# Top.net
KiCad netlist of a schematic drawn in Altium Designer
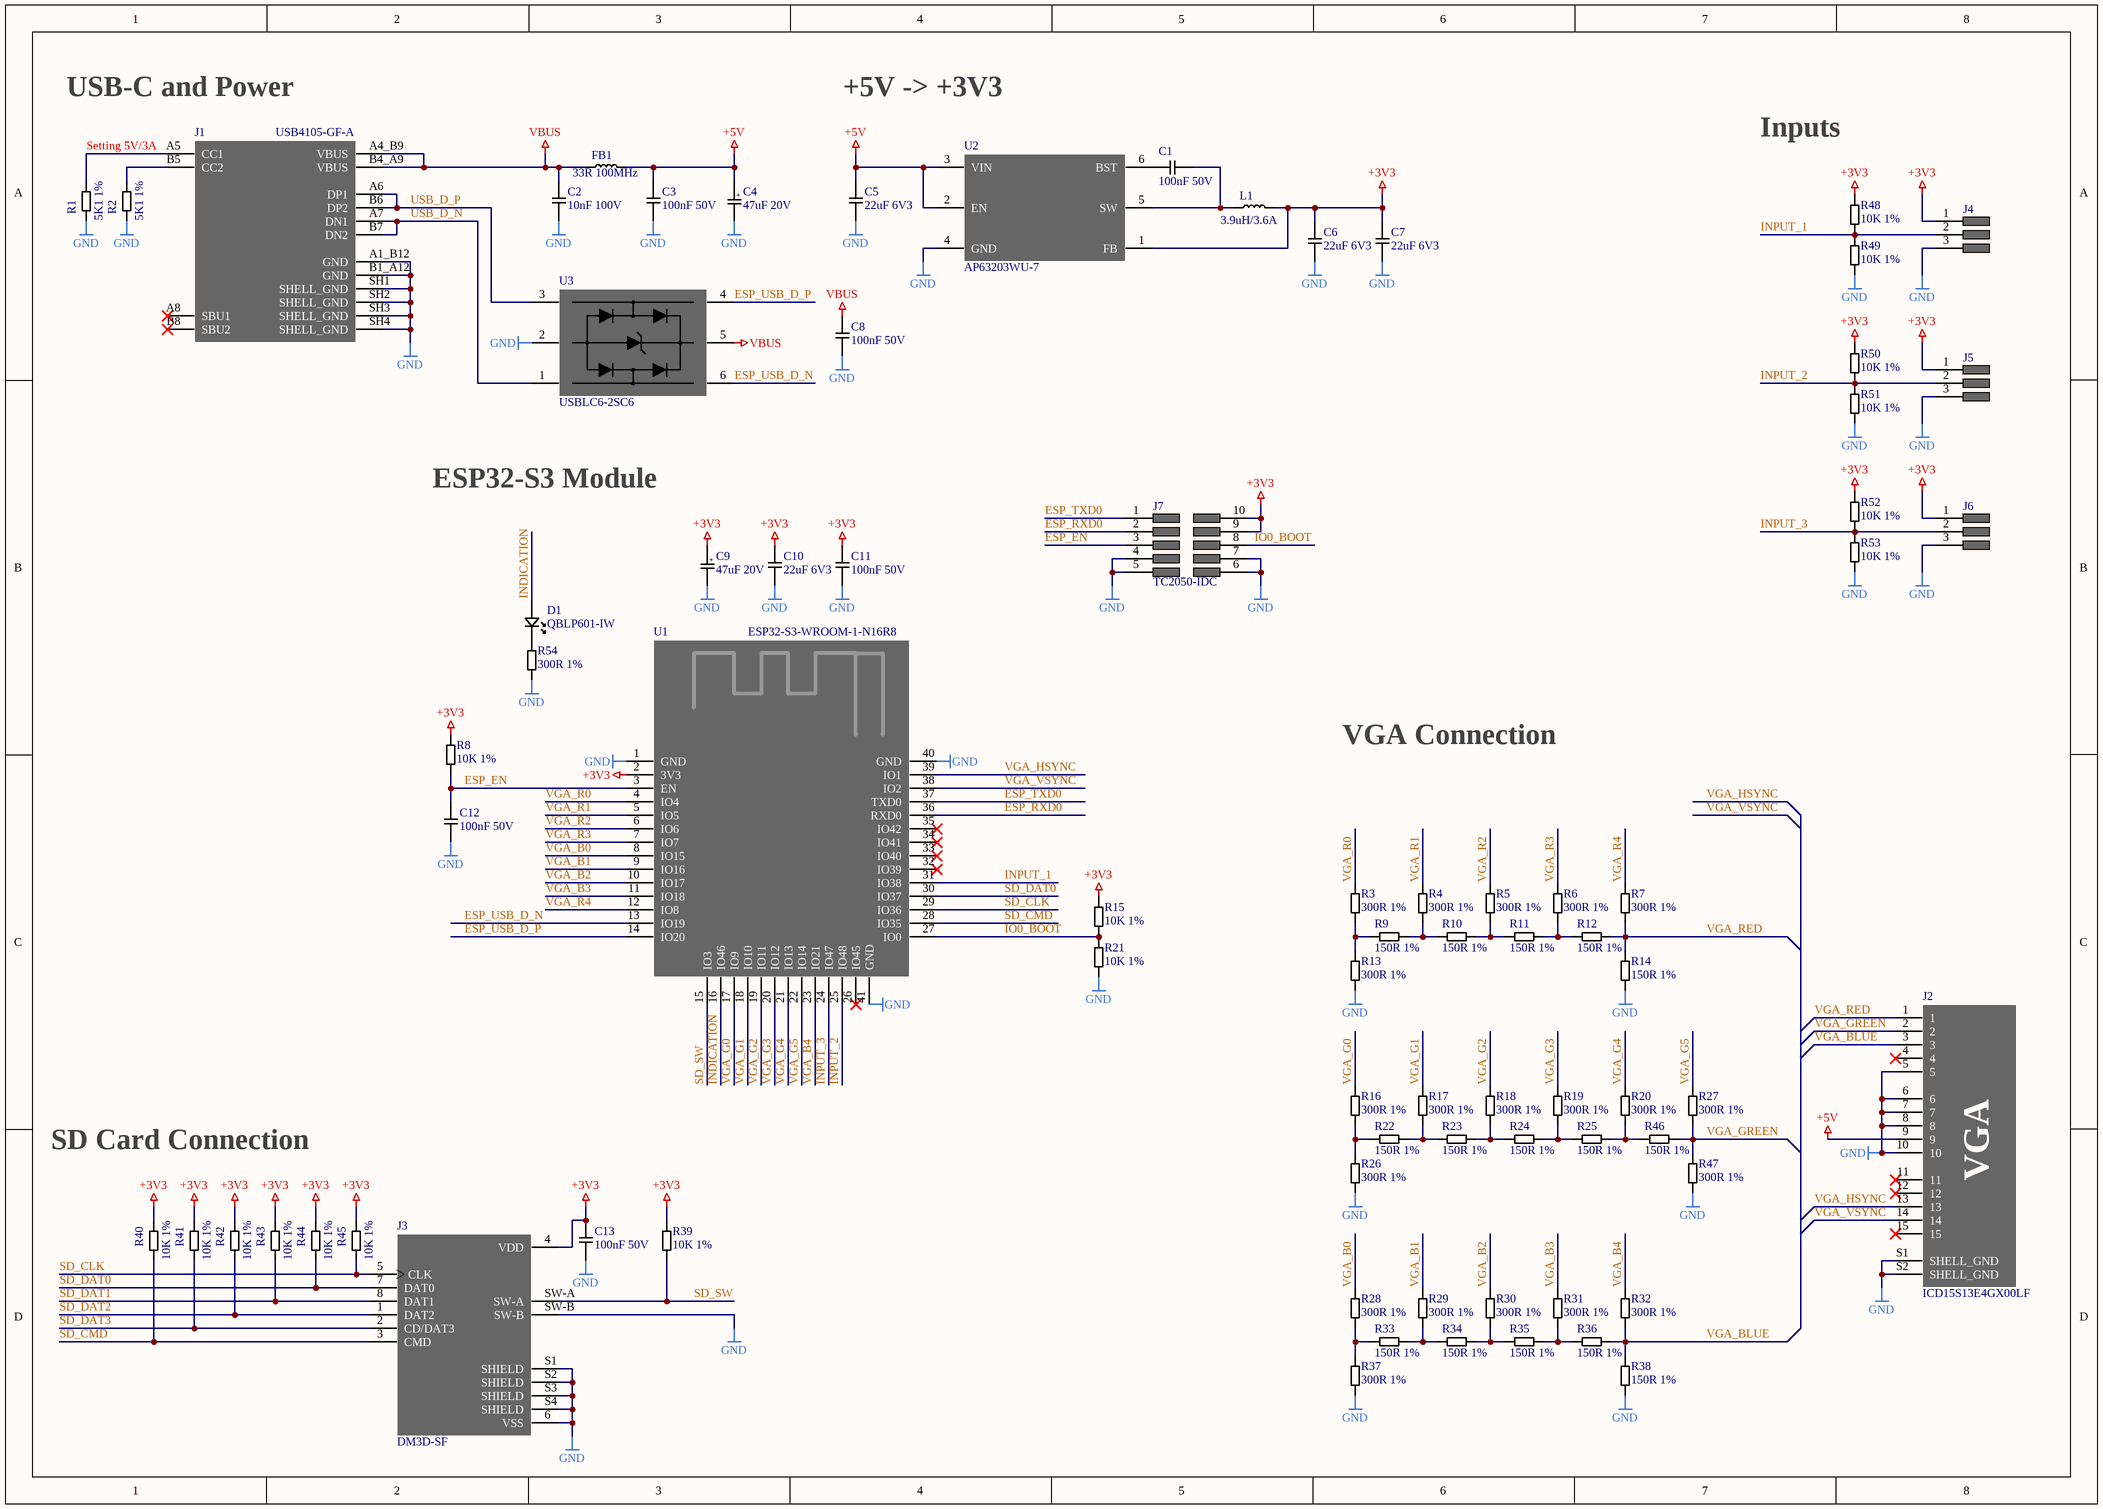
[diagram p0: Top.SchDoc]

(export (version "E")
  (design (tool "Eeschema 10.0.6"))
  (components
    (comp (ref "C1")
      (value "100nF 50V")
      (footprint "CAPC1608X06N")
      (description "0.1 µF ±10% 50V Ceramic Capacitor X7R 0603 (1608 Metric)")
      (fields (field (name "MPN") "GCM188R71H104KA57D"))
      (libsource (lib "VESA-ESP_LIB") (part "100nF 50V"))
    )
    (comp (ref "C2")
      (value "10nF 100V")
      (footprint "CAPC1608X06N")
      (description "10000 pF ±10% 100V Ceramic Capacitor X7R 0603 (1608 Metric)")
      (fields (field (name "MPN") "GCM188R72A103KA37D"))
      (libsource (lib "VESA-ESP_LIB") (part "10nF 100V"))
    )
    (comp (ref "C3")
      (value "100nF 50V")
      (footprint "CAPC1608X06N")
      (description "0.1 µF ±10% 50V Ceramic Capacitor X7R 0603 (1608 Metric)")
      (fields (field (name "MPN") "GCM188R71H104KA57D"))
      (libsource (lib "VESA-ESP_LIB") (part "100nF 50V"))
    )
    (comp (ref "C4")
      (value "47uF 20V")
      (footprint "865080342006")
      (description "47 µF 16 V Aluminum Electrolytic Capacitors Radial, Can - SMD 2000 Hrs @ 105°C")
      (libsource (lib "VESA-ESP_LIB") (part "47uF 20V"))
    )
    (comp (ref "C5")
      (value "22uF 6V3")
      (footprint "CAPC1608X06N")
      (description "22 µF ±20% 6.3V Ceramic Capacitor X5R 0603 (1608 Metric)")
      (fields (field (name "MPN") "GRM188R60J226MEA0D"))
      (libsource (lib "VESA-ESP_LIB") (part "22uF 6V3"))
    )
    (comp (ref "C6")
      (value "22uF 6V3")
      (footprint "CAPC1608X06N")
      (description "22 µF ±20% 6.3V Ceramic Capacitor X5R 0603 (1608 Metric)")
      (fields (field (name "MPN") "GRM188R60J226MEA0D"))
      (libsource (lib "VESA-ESP_LIB") (part "22uF 6V3"))
    )
    (comp (ref "C7")
      (value "22uF 6V3")
      (footprint "CAPC1608X06N")
      (description "22 µF ±20% 6.3V Ceramic Capacitor X5R 0603 (1608 Metric)")
      (fields (field (name "MPN") "GRM188R60J226MEA0D"))
      (libsource (lib "VESA-ESP_LIB") (part "22uF 6V3"))
    )
    (comp (ref "C8")
      (value "100nF 50V")
      (footprint "CAPC1608X06N")
      (description "0.1 µF ±10% 50V Ceramic Capacitor X7R 0603 (1608 Metric)")
      (fields (field (name "MPN") "GCM188R71H104KA57D"))
      (libsource (lib "VESA-ESP_LIB") (part "100nF 50V"))
    )
    (comp (ref "C9")
      (value "47uF 20V")
      (footprint "865080342006")
      (description "47 µF 16 V Aluminum Electrolytic Capacitors Radial, Can - SMD 2000 Hrs @ 105°C")
      (fields (field (name "MPN") "865080342006"))
      (libsource (lib "VESA-ESP_LIB") (part "47uF 20V"))
    )
    (comp (ref "C10")
      (value "22uF 6V3")
      (footprint "CAPC1608X06N")
      (description "22 µF ±20% 6.3V Ceramic Capacitor X5R 0603 (1608 Metric)")
      (fields (field (name "MPN") "GRM188R60J226MEA0D"))
      (libsource (lib "VESA-ESP_LIB") (part "22uF 6V3"))
    )
    (comp (ref "C11")
      (value "100nF 50V")
      (footprint "CAPC1608X06N")
      (description "0.1 µF ±10% 50V Ceramic Capacitor X7R 0603 (1608 Metric)")
      (fields (field (name "MPN") "GCM188R71H104KA57D"))
      (libsource (lib "VESA-ESP_LIB") (part "100nF 50V"))
    )
    (comp (ref "C12")
      (value "100nF 50V")
      (footprint "CAPC1608X06N")
      (description "0.1 µF ±10% 50V Ceramic Capacitor X7R 0603 (1608 Metric)")
      (fields (field (name "MPN") "GCM188R71H104KA57D"))
      (libsource (lib "VESA-ESP_LIB") (part "100nF 50V"))
    )
    (comp (ref "C13")
      (value "100nF 50V")
      (footprint "CAPC1608X06N")
      (description "0.1 µF ±10% 50V Ceramic Capacitor X7R 0603 (1608 Metric)")
      (fields (field (name "MPN") "GCM188R71H104KA57D"))
      (libsource (lib "VESA-ESP_LIB") (part "100nF 50V"))
    )
    (comp (ref "D1")
      (value "QBLP601-IW")
      (footprint "LEDC1608X06N")
      (description "White LED Indication - Discrete 3.2V 0603 (1608 Metric)")
      (libsource (lib "VESA-ESP_LIB") (part "LED WHITE"))
    )
    (comp (ref "FB1")
      (value "33R 100MHz")
      (footprint "INDC1608X06N")
      (description "33 Ohms @ 100 MHz 1 Power Line Ferrite Bead 0603 (1608 Metric) 3A 25mOhm")
      (fields (field (name "MPN") "BLM18PG330SN1D"))
      (libsource (lib "VESA-ESP_LIB") (part "33R 100MHz"))
    )
    (comp (ref "J1")
      (value "USB4105-GF-A")
      (footprint "USB4105-GF-A")
      (libsource (lib "VESA-ESP_LIB") (part "USB4105-GF-A"))
    )
    (comp (ref "J2")
      (value "ICD15S13E4GX00LF")
      (footprint "ICD15S13E4GX00LF")
      (description "15 Position D-Sub, High Density Receptacle, Female Sockets Connector")
      (libsource (lib "VESA-ESP_LIB") (part "ICD15S13E4GX00LF"))
    )
    (comp (ref "J3")
      (value "DM3D-SF")
      (footprint "DM3D-SF")
      (description "10 (8 + 2) Position Card Connector Secure Digital - microSD™ Surface Mount, Right Angle Gold")
      (libsource (lib "VESA-ESP_LIB") (part "DM3D-SF"))
    )
    (comp (ref "J4")
      (value "Conn_2.54mm_3POS")
      (footprint "CONN_2.54MM_3POS")
      (libsource (lib "VESA-ESP_LIB") (part "Conn_2.54mm_3POS"))
    )
    (comp (ref "J5")
      (value "Conn_2.54mm_3POS")
      (footprint "CONN_2.54MM_3POS")
      (libsource (lib "VESA-ESP_LIB") (part "Conn_2.54mm_3POS"))
    )
    (comp (ref "J6")
      (value "Conn_2.54mm_3POS")
      (footprint "CONN_2.54MM_3POS")
      (libsource (lib "VESA-ESP_LIB") (part "Conn_2.54mm_3POS"))
    )
    (comp (ref "J7")
      (value "TC2050-IDC")
      (footprint "TAG_CONNECT")
      (libsource (lib "VESA-ESP_LIB") (part "TC2050-IDC"))
    )
    (comp (ref "L1")
      (value "3.9uH/3.6A")
      (footprint "SDE0604A-3R9M")
      (description "FIXED IND 3.9UH 3.6A 65 MOHM SMD")
      (fields (field (name "MPN") "SDE0604A-3R9M"))
      (libsource (lib "VESA-ESP_LIB") (part "3.9uH/3.6A"))
    )
    (comp (ref "R1")
      (value "5K1 1%")
      (footprint "RESC1608X06N")
      (description "5.1 kOhms ±1% 0.1W, 1/10W Chip Resistor 0603 (1608 Metric) Automotive AEC-Q200 Thick Film")
      (fields (field (name "MPN") "ERJ-3EKF5101V"))
      (libsource (lib "VESA-ESP_LIB") (part "5K1 1%"))
    )
    (comp (ref "R2")
      (value "5K1 1%")
      (footprint "RESC1608X06N")
      (description "5.1 kOhms ±1% 0.1W, 1/10W Chip Resistor 0603 (1608 Metric) Automotive AEC-Q200 Thick Film")
      (fields (field (name "MPN") "ERJ-3EKF5101V"))
      (libsource (lib "VESA-ESP_LIB") (part "5K1 1%"))
    )
    (comp (ref "R3")
      (value "300R 1%")
      (footprint "RESC1608X06N")
      (description "300 Ohms ±1% 0.1W, 1/10W Chip Resistor 0603 (1608 Metric) Automotive AEC-Q200 Thick Film")
      (fields (field (name "MPN") "ERJ-3EKF3000V"))
      (libsource (lib "VESA-ESP_LIB") (part "300R 1%"))
    )
    (comp (ref "R4")
      (value "300R 1%")
      (footprint "RESC1608X06N")
      (description "300 Ohms ±1% 0.1W, 1/10W Chip Resistor 0603 (1608 Metric) Automotive AEC-Q200 Thick Film")
      (fields (field (name "MPN") "ERJ-3EKF3000V"))
      (libsource (lib "VESA-ESP_LIB") (part "300R 1%"))
    )
    (comp (ref "R5")
      (value "300R 1%")
      (footprint "RESC1608X06N")
      (description "300 Ohms ±1% 0.1W, 1/10W Chip Resistor 0603 (1608 Metric) Automotive AEC-Q200 Thick Film")
      (fields (field (name "MPN") "ERJ-3EKF3000V"))
      (libsource (lib "VESA-ESP_LIB") (part "300R 1%"))
    )
    (comp (ref "R6")
      (value "300R 1%")
      (footprint "RESC1608X06N")
      (description "300 Ohms ±1% 0.1W, 1/10W Chip Resistor 0603 (1608 Metric) Automotive AEC-Q200 Thick Film")
      (fields (field (name "MPN") "ERJ-3EKF3000V"))
      (libsource (lib "VESA-ESP_LIB") (part "300R 1%"))
    )
    (comp (ref "R7")
      (value "300R 1%")
      (footprint "RESC1608X06N")
      (description "300 Ohms ±1% 0.1W, 1/10W Chip Resistor 0603 (1608 Metric) Automotive AEC-Q200 Thick Film")
      (fields (field (name "MPN") "ERJ-3EKF3000V"))
      (libsource (lib "VESA-ESP_LIB") (part "300R 1%"))
    )
    (comp (ref "R8")
      (value "10K 1%")
      (footprint "RESC1608X06N")
      (description "10 kOhms ±1% 0.1W, 1/10W Chip Resistor 0603 (1608 Metric) Automotive AEC-Q200 Thick Film")
      (fields (field (name "MPN") "ERJ-3EKF1002V"))
      (libsource (lib "VESA-ESP_LIB") (part "10K 1%"))
    )
    (comp (ref "R9")
      (value "150R 1%")
      (footprint "RESC1608X06N")
      (description "150 Ohms ±1% 0.1W, 1/10W Chip Resistor 0603 (1608 Metric) Automotive AEC-Q200 Thick Film")
      (fields (field (name "MPN") "ERJ-3EKF1500V"))
      (libsource (lib "VESA-ESP_LIB") (part "150R 1%"))
    )
    (comp (ref "R10")
      (value "150R 1%")
      (footprint "RESC1608X06N")
      (description "150 Ohms ±1% 0.1W, 1/10W Chip Resistor 0603 (1608 Metric) Automotive AEC-Q200 Thick Film")
      (fields (field (name "MPN") "ERJ-3EKF1500V"))
      (libsource (lib "VESA-ESP_LIB") (part "150R 1%"))
    )
    (comp (ref "R11")
      (value "150R 1%")
      (footprint "RESC1608X06N")
      (description "150 Ohms ±1% 0.1W, 1/10W Chip Resistor 0603 (1608 Metric) Automotive AEC-Q200 Thick Film")
      (fields (field (name "MPN") "ERJ-3EKF1500V"))
      (libsource (lib "VESA-ESP_LIB") (part "150R 1%"))
    )
    (comp (ref "R12")
      (value "150R 1%")
      (footprint "RESC1608X06N")
      (description "150 Ohms ±1% 0.1W, 1/10W Chip Resistor 0603 (1608 Metric) Automotive AEC-Q200 Thick Film")
      (fields (field (name "MPN") "ERJ-3EKF1500V"))
      (libsource (lib "VESA-ESP_LIB") (part "150R 1%"))
    )
    (comp (ref "R13")
      (value "300R 1%")
      (footprint "RESC1608X06N")
      (description "300 Ohms ±1% 0.1W, 1/10W Chip Resistor 0603 (1608 Metric) Automotive AEC-Q200 Thick Film")
      (fields (field (name "MPN") "ERJ-3EKF3000V"))
      (libsource (lib "VESA-ESP_LIB") (part "300R 1%"))
    )
    (comp (ref "R14")
      (value "150R 1%")
      (footprint "RESC1608X06N")
      (description "150 Ohms ±1% 0.1W, 1/10W Chip Resistor 0603 (1608 Metric) Automotive AEC-Q200 Thick Film")
      (fields (field (name "MPN") "ERJ-3EKF1500V"))
      (libsource (lib "VESA-ESP_LIB") (part "150R 1%"))
    )
    (comp (ref "R15")
      (value "10K 1%")
      (footprint "RESC1608X06N")
      (description "10 kOhms ±1% 0.1W, 1/10W Chip Resistor 0603 (1608 Metric) Automotive AEC-Q200 Thick Film")
      (fields (field (name "MPN") "ERJ-3EKF1002V"))
      (libsource (lib "VESA-ESP_LIB") (part "10K 1%"))
    )
    (comp (ref "R16")
      (value "300R 1%")
      (footprint "RESC1608X06N")
      (description "300 Ohms ±1% 0.1W, 1/10W Chip Resistor 0603 (1608 Metric) Automotive AEC-Q200 Thick Film")
      (fields (field (name "MPN") "ERJ-3EKF3000V"))
      (libsource (lib "VESA-ESP_LIB") (part "300R 1%"))
    )
    (comp (ref "R17")
      (value "300R 1%")
      (footprint "RESC1608X06N")
      (description "300 Ohms ±1% 0.1W, 1/10W Chip Resistor 0603 (1608 Metric) Automotive AEC-Q200 Thick Film")
      (fields (field (name "MPN") "ERJ-3EKF3000V"))
      (libsource (lib "VESA-ESP_LIB") (part "300R 1%"))
    )
    (comp (ref "R18")
      (value "300R 1%")
      (footprint "RESC1608X06N")
      (description "300 Ohms ±1% 0.1W, 1/10W Chip Resistor 0603 (1608 Metric) Automotive AEC-Q200 Thick Film")
      (fields (field (name "MPN") "ERJ-3EKF3000V"))
      (libsource (lib "VESA-ESP_LIB") (part "300R 1%"))
    )
    (comp (ref "R19")
      (value "300R 1%")
      (footprint "RESC1608X06N")
      (description "300 Ohms ±1% 0.1W, 1/10W Chip Resistor 0603 (1608 Metric) Automotive AEC-Q200 Thick Film")
      (fields (field (name "MPN") "ERJ-3EKF3000V"))
      (libsource (lib "VESA-ESP_LIB") (part "300R 1%"))
    )
    (comp (ref "R20")
      (value "300R 1%")
      (footprint "RESC1608X06N")
      (description "300 Ohms ±1% 0.1W, 1/10W Chip Resistor 0603 (1608 Metric) Automotive AEC-Q200 Thick Film")
      (fields (field (name "MPN") "ERJ-3EKF3000V"))
      (libsource (lib "VESA-ESP_LIB") (part "300R 1%"))
    )
    (comp (ref "R21")
      (value "10K 1%")
      (footprint "RESC1608X06N")
      (description "10 kOhms ±1% 0.1W, 1/10W Chip Resistor 0603 (1608 Metric) Automotive AEC-Q200 Thick Film")
      (fields (field (name "MPN") "ERJ-3EKF1002V"))
      (libsource (lib "VESA-ESP_LIB") (part "10K 1%"))
    )
    (comp (ref "R22")
      (value "150R 1%")
      (footprint "RESC1608X06N")
      (description "150 Ohms ±1% 0.1W, 1/10W Chip Resistor 0603 (1608 Metric) Automotive AEC-Q200 Thick Film")
      (fields (field (name "MPN") "ERJ-3EKF1500V"))
      (libsource (lib "VESA-ESP_LIB") (part "150R 1%"))
    )
    (comp (ref "R23")
      (value "150R 1%")
      (footprint "RESC1608X06N")
      (description "150 Ohms ±1% 0.1W, 1/10W Chip Resistor 0603 (1608 Metric) Automotive AEC-Q200 Thick Film")
      (fields (field (name "MPN") "ERJ-3EKF1500V"))
      (libsource (lib "VESA-ESP_LIB") (part "150R 1%"))
    )
    (comp (ref "R24")
      (value "150R 1%")
      (footprint "RESC1608X06N")
      (description "150 Ohms ±1% 0.1W, 1/10W Chip Resistor 0603 (1608 Metric) Automotive AEC-Q200 Thick Film")
      (fields (field (name "MPN") "ERJ-3EKF1500V"))
      (libsource (lib "VESA-ESP_LIB") (part "150R 1%"))
    )
    (comp (ref "R25")
      (value "150R 1%")
      (footprint "RESC1608X06N")
      (description "150 Ohms ±1% 0.1W, 1/10W Chip Resistor 0603 (1608 Metric) Automotive AEC-Q200 Thick Film")
      (fields (field (name "MPN") "ERJ-3EKF1500V"))
      (libsource (lib "VESA-ESP_LIB") (part "150R 1%"))
    )
    (comp (ref "R26")
      (value "300R 1%")
      (footprint "RESC1608X06N")
      (description "300 Ohms ±1% 0.1W, 1/10W Chip Resistor 0603 (1608 Metric) Automotive AEC-Q200 Thick Film")
      (fields (field (name "MPN") "ERJ-3EKF3000V"))
      (libsource (lib "VESA-ESP_LIB") (part "300R 1%"))
    )
    (comp (ref "R27")
      (value "300R 1%")
      (footprint "RESC1608X06N")
      (description "300 Ohms ±1% 0.1W, 1/10W Chip Resistor 0603 (1608 Metric) Automotive AEC-Q200 Thick Film")
      (fields (field (name "MPN") "ERJ-3EKF3000V"))
      (libsource (lib "VESA-ESP_LIB") (part "300R 1%"))
    )
    (comp (ref "R28")
      (value "300R 1%")
      (footprint "RESC1608X06N")
      (description "300 Ohms ±1% 0.1W, 1/10W Chip Resistor 0603 (1608 Metric) Automotive AEC-Q200 Thick Film")
      (fields (field (name "MPN") "ERJ-3EKF3000V"))
      (libsource (lib "VESA-ESP_LIB") (part "300R 1%"))
    )
    (comp (ref "R29")
      (value "300R 1%")
      (footprint "RESC1608X06N")
      (description "300 Ohms ±1% 0.1W, 1/10W Chip Resistor 0603 (1608 Metric) Automotive AEC-Q200 Thick Film")
      (fields (field (name "MPN") "ERJ-3EKF3000V"))
      (libsource (lib "VESA-ESP_LIB") (part "300R 1%"))
    )
    (comp (ref "R30")
      (value "300R 1%")
      (footprint "RESC1608X06N")
      (description "300 Ohms ±1% 0.1W, 1/10W Chip Resistor 0603 (1608 Metric) Automotive AEC-Q200 Thick Film")
      (fields (field (name "MPN") "ERJ-3EKF3000V"))
      (libsource (lib "VESA-ESP_LIB") (part "300R 1%"))
    )
    (comp (ref "R31")
      (value "300R 1%")
      (footprint "RESC1608X06N")
      (description "300 Ohms ±1% 0.1W, 1/10W Chip Resistor 0603 (1608 Metric) Automotive AEC-Q200 Thick Film")
      (fields (field (name "MPN") "ERJ-3EKF3000V"))
      (libsource (lib "VESA-ESP_LIB") (part "300R 1%"))
    )
    (comp (ref "R32")
      (value "300R 1%")
      (footprint "RESC1608X06N")
      (description "300 Ohms ±1% 0.1W, 1/10W Chip Resistor 0603 (1608 Metric) Automotive AEC-Q200 Thick Film")
      (fields (field (name "MPN") "ERJ-3EKF3000V"))
      (libsource (lib "VESA-ESP_LIB") (part "300R 1%"))
    )
    (comp (ref "R33")
      (value "150R 1%")
      (footprint "RESC1608X06N")
      (description "150 Ohms ±1% 0.1W, 1/10W Chip Resistor 0603 (1608 Metric) Automotive AEC-Q200 Thick Film")
      (fields (field (name "MPN") "ERJ-3EKF1500V"))
      (libsource (lib "VESA-ESP_LIB") (part "150R 1%"))
    )
    (comp (ref "R34")
      (value "150R 1%")
      (footprint "RESC1608X06N")
      (description "150 Ohms ±1% 0.1W, 1/10W Chip Resistor 0603 (1608 Metric) Automotive AEC-Q200 Thick Film")
      (fields (field (name "MPN") "ERJ-3EKF1500V"))
      (libsource (lib "VESA-ESP_LIB") (part "150R 1%"))
    )
    (comp (ref "R35")
      (value "150R 1%")
      (footprint "RESC1608X06N")
      (description "150 Ohms ±1% 0.1W, 1/10W Chip Resistor 0603 (1608 Metric) Automotive AEC-Q200 Thick Film")
      (fields (field (name "MPN") "ERJ-3EKF1500V"))
      (libsource (lib "VESA-ESP_LIB") (part "150R 1%"))
    )
    (comp (ref "R36")
      (value "150R 1%")
      (footprint "RESC1608X06N")
      (description "150 Ohms ±1% 0.1W, 1/10W Chip Resistor 0603 (1608 Metric) Automotive AEC-Q200 Thick Film")
      (fields (field (name "MPN") "ERJ-3EKF1500V"))
      (libsource (lib "VESA-ESP_LIB") (part "150R 1%"))
    )
    (comp (ref "R37")
      (value "300R 1%")
      (footprint "RESC1608X06N")
      (description "300 Ohms ±1% 0.1W, 1/10W Chip Resistor 0603 (1608 Metric) Automotive AEC-Q200 Thick Film")
      (fields (field (name "MPN") "ERJ-3EKF3000V"))
      (libsource (lib "VESA-ESP_LIB") (part "300R 1%"))
    )
    (comp (ref "R38")
      (value "150R 1%")
      (footprint "RESC1608X06N")
      (description "150 Ohms ±1% 0.1W, 1/10W Chip Resistor 0603 (1608 Metric) Automotive AEC-Q200 Thick Film")
      (fields (field (name "MPN") "ERJ-3EKF1500V"))
      (libsource (lib "VESA-ESP_LIB") (part "150R 1%"))
    )
    (comp (ref "R39")
      (value "10K 1%")
      (footprint "RESC1608X06N")
      (description "10 kOhms ±1% 0.1W, 1/10W Chip Resistor 0603 (1608 Metric) Automotive AEC-Q200 Thick Film")
      (fields (field (name "MPN") "ERJ-3EKF1002V"))
      (libsource (lib "VESA-ESP_LIB") (part "10K 1%"))
    )
    (comp (ref "R40")
      (value "10K 1%")
      (footprint "RESC1608X06N")
      (description "10 kOhms ±1% 0.1W, 1/10W Chip Resistor 0603 (1608 Metric) Automotive AEC-Q200 Thick Film")
      (fields (field (name "MPN") "ERJ-3EKF1002V"))
      (libsource (lib "VESA-ESP_LIB") (part "10K 1%"))
    )
    (comp (ref "R41")
      (value "10K 1%")
      (footprint "RESC1608X06N")
      (description "10 kOhms ±1% 0.1W, 1/10W Chip Resistor 0603 (1608 Metric) Automotive AEC-Q200 Thick Film")
      (fields (field (name "MPN") "ERJ-3EKF1002V"))
      (libsource (lib "VESA-ESP_LIB") (part "10K 1%"))
    )
    (comp (ref "R42")
      (value "10K 1%")
      (footprint "RESC1608X06N")
      (description "10 kOhms ±1% 0.1W, 1/10W Chip Resistor 0603 (1608 Metric) Automotive AEC-Q200 Thick Film")
      (fields (field (name "MPN") "ERJ-3EKF1002V"))
      (libsource (lib "VESA-ESP_LIB") (part "10K 1%"))
    )
    (comp (ref "R43")
      (value "10K 1%")
      (footprint "RESC1608X06N")
      (description "10 kOhms ±1% 0.1W, 1/10W Chip Resistor 0603 (1608 Metric) Automotive AEC-Q200 Thick Film")
      (fields (field (name "MPN") "ERJ-3EKF1002V"))
      (libsource (lib "VESA-ESP_LIB") (part "10K 1%"))
    )
    (comp (ref "R44")
      (value "10K 1%")
      (footprint "RESC1608X06N")
      (description "10 kOhms ±1% 0.1W, 1/10W Chip Resistor 0603 (1608 Metric) Automotive AEC-Q200 Thick Film")
      (fields (field (name "MPN") "ERJ-3EKF1002V"))
      (libsource (lib "VESA-ESP_LIB") (part "10K 1%"))
    )
    (comp (ref "R45")
      (value "10K 1%")
      (footprint "RESC1608X06N")
      (description "10 kOhms ±1% 0.1W, 1/10W Chip Resistor 0603 (1608 Metric) Automotive AEC-Q200 Thick Film")
      (fields (field (name "MPN") "ERJ-3EKF1002V"))
      (libsource (lib "VESA-ESP_LIB") (part "10K 1%"))
    )
    (comp (ref "R46")
      (value "150R 1%")
      (footprint "RESC1608X06N")
      (description "150 Ohms ±1% 0.1W, 1/10W Chip Resistor 0603 (1608 Metric) Automotive AEC-Q200 Thick Film")
      (fields (field (name "MPN") "ERJ-3EKF1500V"))
      (libsource (lib "VESA-ESP_LIB") (part "150R 1%"))
    )
    (comp (ref "R47")
      (value "300R 1%")
      (footprint "RESC1608X06N")
      (description "300 Ohms ±1% 0.1W, 1/10W Chip Resistor 0603 (1608 Metric) Automotive AEC-Q200 Thick Film")
      (fields (field (name "MPN") "ERJ-3EKF3000V"))
      (libsource (lib "VESA-ESP_LIB") (part "300R 1%"))
    )
    (comp (ref "R48")
      (value "10K 1%")
      (footprint "RESC1608X06N")
      (description "10 kOhms ±1% 0.1W, 1/10W Chip Resistor 0603 (1608 Metric) Automotive AEC-Q200 Thick Film")
      (fields (field (name "MPN") "ERJ-3EKF1002V"))
      (libsource (lib "VESA-ESP_LIB") (part "10K 1%"))
    )
    (comp (ref "R49")
      (value "10K 1%")
      (footprint "RESC1608X06N")
      (description "10 kOhms ±1% 0.1W, 1/10W Chip Resistor 0603 (1608 Metric) Automotive AEC-Q200 Thick Film")
      (fields (field (name "MPN") "ERJ-3EKF1002V"))
      (libsource (lib "VESA-ESP_LIB") (part "10K 1%"))
    )
    (comp (ref "R50")
      (value "10K 1%")
      (footprint "RESC1608X06N")
      (description "10 kOhms ±1% 0.1W, 1/10W Chip Resistor 0603 (1608 Metric) Automotive AEC-Q200 Thick Film")
      (fields (field (name "MPN") "ERJ-3EKF1002V"))
      (libsource (lib "VESA-ESP_LIB") (part "10K 1%"))
    )
    (comp (ref "R51")
      (value "10K 1%")
      (footprint "RESC1608X06N")
      (description "10 kOhms ±1% 0.1W, 1/10W Chip Resistor 0603 (1608 Metric) Automotive AEC-Q200 Thick Film")
      (fields (field (name "MPN") "ERJ-3EKF1002V"))
      (libsource (lib "VESA-ESP_LIB") (part "10K 1%"))
    )
    (comp (ref "R52")
      (value "10K 1%")
      (footprint "RESC1608X06N")
      (description "10 kOhms ±1% 0.1W, 1/10W Chip Resistor 0603 (1608 Metric) Automotive AEC-Q200 Thick Film")
      (fields (field (name "MPN") "ERJ-3EKF1002V"))
      (libsource (lib "VESA-ESP_LIB") (part "10K 1%"))
    )
    (comp (ref "R53")
      (value "10K 1%")
      (footprint "RESC1608X06N")
      (description "10 kOhms ±1% 0.1W, 1/10W Chip Resistor 0603 (1608 Metric) Automotive AEC-Q200 Thick Film")
      (fields (field (name "MPN") "ERJ-3EKF1002V"))
      (libsource (lib "VESA-ESP_LIB") (part "10K 1%"))
    )
    (comp (ref "R54")
      (value "300R 1%")
      (footprint "RESC1608X06N")
      (description "300 Ohms ±1% 0.1W, 1/10W Chip Resistor 0603 (1608 Metric) Automotive AEC-Q200 Thick Film")
      (fields (field (name "MPN") "ERJ-3EKF3000V"))
      (libsource (lib "VESA-ESP_LIB") (part "300R 1%"))
    )
    (comp (ref "U1")
      (value "ESP32-S3-WROOM-1-N16R8")
      (footprint "ESP32-S3-WROOM")
      (description "Bluetooth, WiFi 802.11b/g/n, Bluetooth v5.0 Transceiver Module 2.4GHz PCB Trace Surface Mount")
      (libsource (lib "VESA-ESP_LIB") (part "ESP32-S3-WROOM-1-N16R8"))
    )
    (comp (ref "U2")
      (value "AP63203WU-7")
      (footprint "SOT95P245X100-6N")
      (description "Buck Switching Regulator IC Positive Fixed 3.3V 1 Output 2A SOT-23-6 Thin, TSOT-23-6")
      (libsource (lib "VESA-ESP_LIB") (part "AP63203WU-7"))
    )
    (comp (ref "U3")
      (value "USBLC6-2SC6")
      (footprint "SOT95P245X100-6N")
      (description "17V Clamp 5A (8/20µs) Ipp Tvs Diode Surface Mount SOT-23-6")
      (libsource (lib "VESA-ESP_LIB") (part "USBLC6-2SC6"))
    )
  )
  (nets
    (net (code "1") (name "+3V3") (class "Default")
      (node (ref "C10") (pin "2") (pinfunction "2_2") (pintype "passive"))
      (node (ref "C11") (pin "2") (pinfunction "2_2") (pintype "passive"))
      (node (ref "C13") (pin "2") (pinfunction "2_2") (pintype "passive"))
      (node (ref "C6") (pin "2") (pinfunction "2_2") (pintype "passive"))
      (node (ref "C7") (pin "2") (pinfunction "2_2") (pintype "passive"))
      (node (ref "C9") (pin "1") (pinfunction "1_1") (pintype "passive"))
      (node (ref "J3") (pin "4") (pinfunction "VDD_4") (pintype "passive"))
      (node (ref "J4") (pin "1") (pinfunction "1_1") (pintype "passive"))
      (node (ref "J5") (pin "1") (pinfunction "1_1") (pintype "passive"))
      (node (ref "J6") (pin "1") (pinfunction "1_1") (pintype "passive"))
      (node (ref "J7") (pin "10") (pinfunction "10_10") (pintype "passive"))
      (node (ref "J7") (pin "9") (pinfunction "9_9") (pintype "passive"))
      (node (ref "L1") (pin "2") (pinfunction "2_2") (pintype "passive"))
      (node (ref "R15") (pin "1") (pinfunction "1_1") (pintype "passive"))
      (node (ref "R39") (pin "1") (pinfunction "1_1") (pintype "passive"))
      (node (ref "R40") (pin "1") (pinfunction "1_1") (pintype "passive"))
      (node (ref "R41") (pin "1") (pinfunction "1_1") (pintype "passive"))
      (node (ref "R42") (pin "1") (pinfunction "1_1") (pintype "passive"))
      (node (ref "R43") (pin "1") (pinfunction "1_1") (pintype "passive"))
      (node (ref "R44") (pin "1") (pinfunction "1_1") (pintype "passive"))
      (node (ref "R45") (pin "1") (pinfunction "1_1") (pintype "passive"))
      (node (ref "R48") (pin "1") (pinfunction "1_1") (pintype "passive"))
      (node (ref "R50") (pin "1") (pinfunction "1_1") (pintype "passive"))
      (node (ref "R52") (pin "1") (pinfunction "1_1") (pintype "passive"))
      (node (ref "R8") (pin "1") (pinfunction "1_1") (pintype "passive"))
      (node (ref "U1") (pin "2") (pinfunction "3V3_2") (pintype "passive"))
      (node (ref "U2") (pin "1") (pinfunction "FB_1") (pintype "passive"))
    )
    (net (code "2") (name "+5V") (class "Default")
      (node (ref "C3") (pin "2") (pinfunction "2_2") (pintype "passive"))
      (node (ref "C4") (pin "1") (pinfunction "1_1") (pintype "passive"))
      (node (ref "C5") (pin "2") (pinfunction "2_2") (pintype "passive"))
      (node (ref "FB1") (pin "2") (pinfunction "2_2") (pintype "passive"))
      (node (ref "J2") (pin "9") (pinfunction "9_9") (pintype "passive"))
      (node (ref "U2") (pin "2") (pinfunction "EN_2") (pintype "passive"))
      (node (ref "U2") (pin "3") (pinfunction "VIN_3") (pintype "passive"))
    )
    (net (code "3") (name "/ESP_EN") (class "Default")
      (node (ref "C12") (pin "2") (pinfunction "2_2") (pintype "passive"))
      (node (ref "J7") (pin "3") (pinfunction "3_3") (pintype "passive"))
      (node (ref "R8") (pin "2") (pinfunction "2_2") (pintype "passive"))
      (node (ref "U1") (pin "3") (pinfunction "EN_3") (pintype "passive"))
    )
    (net (code "4") (name "/ESP_RXD0") (class "Default")
      (node (ref "J7") (pin "2") (pinfunction "2_2") (pintype "passive"))
      (node (ref "U1") (pin "36") (pinfunction "RXD0_36") (pintype "passive"))
    )
    (net (code "5") (name "/ESP_TXD0") (class "Default")
      (node (ref "J7") (pin "1") (pinfunction "1_1") (pintype "passive"))
      (node (ref "U1") (pin "37") (pinfunction "TXD0_37") (pintype "passive"))
    )
    (net (code "6") (name "/ESP_USB_D_N") (class "Default")
      (node (ref "U1") (pin "13") (pinfunction "IO19_13") (pintype "passive"))
      (node (ref "U3") (pin "6") (pinfunction "6_6") (pintype "passive"))
    )
    (net (code "7") (name "/ESP_USB_D_P") (class "Default")
      (node (ref "U1") (pin "14") (pinfunction "IO20_14") (pintype "passive"))
      (node (ref "U3") (pin "4") (pinfunction "4_4") (pintype "passive"))
    )
    (net (code "8") (name "/INDICATION") (class "Default")
      (node (ref "D1") (pin "1") (pinfunction "1_1") (pintype "passive"))
      (node (ref "U1") (pin "16") (pinfunction "IO46_16") (pintype "passive"))
    )
    (net (code "9") (name "/INPUT_1") (class "Default")
      (node (ref "J4") (pin "2") (pinfunction "2_2") (pintype "passive"))
      (node (ref "R48") (pin "2") (pinfunction "2_2") (pintype "passive"))
      (node (ref "R49") (pin "1") (pinfunction "1_1") (pintype "passive"))
      (node (ref "U1") (pin "31") (pinfunction "IO38_31") (pintype "passive"))
    )
    (net (code "10") (name "/INPUT_2") (class "Default")
      (node (ref "J5") (pin "2") (pinfunction "2_2") (pintype "passive"))
      (node (ref "R50") (pin "2") (pinfunction "2_2") (pintype "passive"))
      (node (ref "R51") (pin "1") (pinfunction "1_1") (pintype "passive"))
      (node (ref "U1") (pin "25") (pinfunction "IO48_25") (pintype "passive"))
    )
    (net (code "11") (name "/INPUT_3") (class "Default")
      (node (ref "J6") (pin "2") (pinfunction "2_2") (pintype "passive"))
      (node (ref "R52") (pin "2") (pinfunction "2_2") (pintype "passive"))
      (node (ref "R53") (pin "1") (pinfunction "1_1") (pintype "passive"))
      (node (ref "U1") (pin "24") (pinfunction "IO47_24") (pintype "passive"))
    )
    (net (code "12") (name "/IO0_BOOT") (class "Default")
      (node (ref "J7") (pin "8") (pinfunction "8_8") (pintype "passive"))
      (node (ref "R15") (pin "2") (pinfunction "2_2") (pintype "passive"))
      (node (ref "R21") (pin "1") (pinfunction "1_1") (pintype "passive"))
      (node (ref "U1") (pin "27") (pinfunction "IO0_27") (pintype "passive"))
    )
    (net (code "13") (name "/SD_CLK") (class "Default")
      (node (ref "J3") (pin "5") (pinfunction "CLK_5") (pintype "passive"))
      (node (ref "R45") (pin "2") (pinfunction "2_2") (pintype "passive"))
      (node (ref "U1") (pin "29") (pinfunction "IO36_29") (pintype "passive"))
    )
    (net (code "14") (name "/SD_CMD") (class "Default")
      (node (ref "J3") (pin "3") (pinfunction "CMD_3") (pintype "passive"))
      (node (ref "R40") (pin "2") (pinfunction "2_2") (pintype "passive"))
      (node (ref "U1") (pin "28") (pinfunction "IO35_28") (pintype "passive"))
    )
    (net (code "15") (name "/SD_DAT0") (class "Default")
      (node (ref "J3") (pin "7") (pinfunction "DAT0_7") (pintype "passive"))
      (node (ref "R44") (pin "2") (pinfunction "2_2") (pintype "passive"))
      (node (ref "U1") (pin "30") (pinfunction "IO37_30") (pintype "passive"))
    )
    (net (code "16") (name "/SD_DAT1") (class "Default")
      (node (ref "J3") (pin "8") (pinfunction "DAT1_8") (pintype "passive"))
      (node (ref "R43") (pin "2") (pinfunction "2_2") (pintype "passive"))
    )
    (net (code "17") (name "/SD_DAT2") (class "Default")
      (node (ref "J3") (pin "1") (pinfunction "DAT2_1") (pintype "passive"))
      (node (ref "R42") (pin "2") (pinfunction "2_2") (pintype "passive"))
    )
    (net (code "18") (name "/SD_DAT3") (class "Default")
      (node (ref "J3") (pin "2") (pinfunction "CD/DAT3_2") (pintype "passive"))
      (node (ref "R41") (pin "2") (pinfunction "2_2") (pintype "passive"))
    )
    (net (code "19") (name "/SD_SW") (class "Default")
      (node (ref "J3") (pin "SW-A") (pinfunction "SW-A_SW-A") (pintype "passive"))
      (node (ref "R39") (pin "2") (pinfunction "2_2") (pintype "passive"))
      (node (ref "U1") (pin "15") (pinfunction "IO3_15") (pintype "passive"))
    )
    (net (code "20") (name "/USB_D_N") (class "Default")
      (node (ref "J1") (pin "A7") (pinfunction "DN1_A7") (pintype "passive"))
      (node (ref "J1") (pin "B7") (pinfunction "DN2_B7") (pintype "passive"))
      (node (ref "U3") (pin "1") (pinfunction "1_1") (pintype "passive"))
    )
    (net (code "21") (name "/USB_D_P") (class "Default")
      (node (ref "J1") (pin "A6") (pinfunction "DP1_A6") (pintype "passive"))
      (node (ref "J1") (pin "B6") (pinfunction "DP2_B6") (pintype "passive"))
      (node (ref "U3") (pin "3") (pinfunction "3_3") (pintype "passive"))
    )
    (net (code "22") (name "/VGA_B0") (class "Default")
      (node (ref "R28") (pin "1") (pinfunction "1_1") (pintype "passive"))
      (node (ref "U1") (pin "8") (pinfunction "IO15_8") (pintype "passive"))
    )
    (net (code "23") (name "/VGA_B1") (class "Default")
      (node (ref "R29") (pin "1") (pinfunction "1_1") (pintype "passive"))
      (node (ref "U1") (pin "9") (pinfunction "IO16_9") (pintype "passive"))
    )
    (net (code "24") (name "/VGA_B2") (class "Default")
      (node (ref "R30") (pin "1") (pinfunction "1_1") (pintype "passive"))
      (node (ref "U1") (pin "10") (pinfunction "IO17_10") (pintype "passive"))
    )
    (net (code "25") (name "/VGA_B3") (class "Default")
      (node (ref "R31") (pin "1") (pinfunction "1_1") (pintype "passive"))
      (node (ref "U1") (pin "11") (pinfunction "IO18_11") (pintype "passive"))
    )
    (net (code "26") (name "/VGA_B4") (class "Default")
      (node (ref "R32") (pin "1") (pinfunction "1_1") (pintype "passive"))
      (node (ref "U1") (pin "23") (pinfunction "IO21_23") (pintype "passive"))
    )
    (net (code "27") (name "/VGA_BLUE") (class "Default")
      (node (ref "J2") (pin "3") (pinfunction "3_3") (pintype "passive"))
      (node (ref "R32") (pin "2") (pinfunction "2_2") (pintype "passive"))
      (node (ref "R36") (pin "2") (pinfunction "2_2") (pintype "passive"))
      (node (ref "R38") (pin "1") (pinfunction "1_1") (pintype "passive"))
    )
    (net (code "28") (name "/VGA_G0") (class "Default")
      (node (ref "R16") (pin "1") (pinfunction "1_1") (pintype "passive"))
      (node (ref "U1") (pin "17") (pinfunction "IO9_17") (pintype "passive"))
    )
    (net (code "29") (name "/VGA_G1") (class "Default")
      (node (ref "R17") (pin "1") (pinfunction "1_1") (pintype "passive"))
      (node (ref "U1") (pin "18") (pinfunction "IO10_18") (pintype "passive"))
    )
    (net (code "30") (name "/VGA_G2") (class "Default")
      (node (ref "R18") (pin "1") (pinfunction "1_1") (pintype "passive"))
      (node (ref "U1") (pin "19") (pinfunction "IO11_19") (pintype "passive"))
    )
    (net (code "31") (name "/VGA_G3") (class "Default")
      (node (ref "R19") (pin "1") (pinfunction "1_1") (pintype "passive"))
      (node (ref "U1") (pin "20") (pinfunction "IO12_20") (pintype "passive"))
    )
    (net (code "32") (name "/VGA_G4") (class "Default")
      (node (ref "R20") (pin "1") (pinfunction "1_1") (pintype "passive"))
      (node (ref "U1") (pin "21") (pinfunction "IO13_21") (pintype "passive"))
    )
    (net (code "33") (name "/VGA_G5") (class "Default")
      (node (ref "R27") (pin "1") (pinfunction "1_1") (pintype "passive"))
      (node (ref "U1") (pin "22") (pinfunction "IO14_22") (pintype "passive"))
    )
    (net (code "34") (name "/VGA_GREEN") (class "Default")
      (node (ref "J2") (pin "2") (pinfunction "2_2") (pintype "passive"))
      (node (ref "R27") (pin "2") (pinfunction "2_2") (pintype "passive"))
      (node (ref "R46") (pin "2") (pinfunction "2_2") (pintype "passive"))
      (node (ref "R47") (pin "2") (pinfunction "2_2") (pintype "passive"))
    )
    (net (code "35") (name "/VGA_HSYNC") (class "Default")
      (node (ref "J2") (pin "13") (pinfunction "13_13") (pintype "passive"))
      (node (ref "U1") (pin "39") (pinfunction "IO1_39") (pintype "passive"))
    )
    (net (code "36") (name "/VGA_R0") (class "Default")
      (node (ref "R3") (pin "1") (pinfunction "1_1") (pintype "passive"))
      (node (ref "U1") (pin "4") (pinfunction "IO4_4") (pintype "passive"))
    )
    (net (code "37") (name "/VGA_R1") (class "Default")
      (node (ref "R4") (pin "1") (pinfunction "1_1") (pintype "passive"))
      (node (ref "U1") (pin "5") (pinfunction "IO5_5") (pintype "passive"))
    )
    (net (code "38") (name "/VGA_R2") (class "Default")
      (node (ref "R5") (pin "1") (pinfunction "1_1") (pintype "passive"))
      (node (ref "U1") (pin "6") (pinfunction "IO6_6") (pintype "passive"))
    )
    (net (code "39") (name "/VGA_R3") (class "Default")
      (node (ref "R6") (pin "1") (pinfunction "1_1") (pintype "passive"))
      (node (ref "U1") (pin "7") (pinfunction "IO7_7") (pintype "passive"))
    )
    (net (code "40") (name "/VGA_R4") (class "Default")
      (node (ref "R7") (pin "1") (pinfunction "1_1") (pintype "passive"))
      (node (ref "U1") (pin "12") (pinfunction "IO8_12") (pintype "passive"))
    )
    (net (code "41") (name "/VGA_RED") (class "Default")
      (node (ref "J2") (pin "1") (pinfunction "1_1") (pintype "passive"))
      (node (ref "R12") (pin "2") (pinfunction "2_2") (pintype "passive"))
      (node (ref "R14") (pin "1") (pinfunction "1_1") (pintype "passive"))
      (node (ref "R7") (pin "2") (pinfunction "2_2") (pintype "passive"))
    )
    (net (code "42") (name "/VGA_VSYNC") (class "Default")
      (node (ref "J2") (pin "14") (pinfunction "14_14") (pintype "passive"))
      (node (ref "U1") (pin "38") (pinfunction "IO2_38") (pintype "passive"))
    )
    (net (code "43") (name "GND") (class "Default")
      (node (ref "C10") (pin "1") (pinfunction "1_1") (pintype "passive"))
      (node (ref "C11") (pin "1") (pinfunction "1_1") (pintype "passive"))
      (node (ref "C12") (pin "1") (pinfunction "1_1") (pintype "passive"))
      (node (ref "C13") (pin "1") (pinfunction "1_1") (pintype "passive"))
      (node (ref "C2") (pin "1") (pinfunction "1_1") (pintype "passive"))
      (node (ref "C3") (pin "1") (pinfunction "1_1") (pintype "passive"))
      (node (ref "C4") (pin "2") (pinfunction "2_2") (pintype "passive"))
      (node (ref "C5") (pin "1") (pinfunction "1_1") (pintype "passive"))
      (node (ref "C6") (pin "1") (pinfunction "1_1") (pintype "passive"))
      (node (ref "C7") (pin "1") (pinfunction "1_1") (pintype "passive"))
      (node (ref "C8") (pin "1") (pinfunction "1_1") (pintype "passive"))
      (node (ref "C9") (pin "2") (pinfunction "2_2") (pintype "passive"))
      (node (ref "J1") (pin "A1_B12") (pinfunction "GND_A1_B12") (pintype "passive"))
      (node (ref "J1") (pin "B1_A12") (pinfunction "GND_B1_A12") (pintype "passive"))
      (node (ref "J1") (pin "SH1") (pinfunction "SHELL_GND_SH1") (pintype "passive"))
      (node (ref "J1") (pin "SH2") (pinfunction "SHELL_GND_SH2") (pintype "passive"))
      (node (ref "J1") (pin "SH3") (pinfunction "SHELL_GND_SH3") (pintype "passive"))
      (node (ref "J1") (pin "SH4") (pinfunction "SHELL_GND_SH4") (pintype "passive"))
      (node (ref "J2") (pin "10") (pinfunction "10_10") (pintype "passive"))
      (node (ref "J2") (pin "5") (pinfunction "5_5") (pintype "passive"))
      (node (ref "J2") (pin "6") (pinfunction "6_6") (pintype "passive"))
      (node (ref "J2") (pin "7") (pinfunction "7_7") (pintype "passive"))
      (node (ref "J2") (pin "8") (pinfunction "8_8") (pintype "passive"))
      (node (ref "J2") (pin "S1") (pinfunction "SHELL_GND_S1") (pintype "passive"))
      (node (ref "J2") (pin "S2") (pinfunction "SHELL_GND_S2") (pintype "passive"))
      (node (ref "J3") (pin "6") (pinfunction "VSS_6") (pintype "passive"))
      (node (ref "J3") (pin "S1") (pinfunction "SHIELD_S1") (pintype "passive"))
      (node (ref "J3") (pin "S2") (pinfunction "SHIELD_S2") (pintype "passive"))
      (node (ref "J3") (pin "S3") (pinfunction "SHIELD_S3") (pintype "passive"))
      (node (ref "J3") (pin "S4") (pinfunction "SHIELD_S4") (pintype "passive"))
      (node (ref "J3") (pin "SW-B") (pinfunction "SW-B_SW-B") (pintype "passive"))
      (node (ref "J4") (pin "3") (pinfunction "3_3") (pintype "passive"))
      (node (ref "J5") (pin "3") (pinfunction "3_3") (pintype "passive"))
      (node (ref "J6") (pin "3") (pinfunction "3_3") (pintype "passive"))
      (node (ref "J7") (pin "4") (pinfunction "4_4") (pintype "passive"))
      (node (ref "J7") (pin "5") (pinfunction "5_5") (pintype "passive"))
      (node (ref "J7") (pin "6") (pinfunction "6_6") (pintype "passive"))
      (node (ref "J7") (pin "7") (pinfunction "7_7") (pintype "passive"))
      (node (ref "R1") (pin "1") (pinfunction "1_1") (pintype "passive"))
      (node (ref "R13") (pin "1") (pinfunction "1_1") (pintype "passive"))
      (node (ref "R14") (pin "2") (pinfunction "2_2") (pintype "passive"))
      (node (ref "R2") (pin "1") (pinfunction "1_1") (pintype "passive"))
      (node (ref "R21") (pin "2") (pinfunction "2_2") (pintype "passive"))
      (node (ref "R26") (pin "1") (pinfunction "1_1") (pintype "passive"))
      (node (ref "R37") (pin "1") (pinfunction "1_1") (pintype "passive"))
      (node (ref "R38") (pin "2") (pinfunction "2_2") (pintype "passive"))
      (node (ref "R47") (pin "1") (pinfunction "1_1") (pintype "passive"))
      (node (ref "R49") (pin "2") (pinfunction "2_2") (pintype "passive"))
      (node (ref "R51") (pin "2") (pinfunction "2_2") (pintype "passive"))
      (node (ref "R53") (pin "2") (pinfunction "2_2") (pintype "passive"))
      (node (ref "R54") (pin "1") (pinfunction "1_1") (pintype "passive"))
      (node (ref "U1") (pin "1") (pinfunction "GND_1") (pintype "passive"))
      (node (ref "U1") (pin "40") (pinfunction "GND_40") (pintype "passive"))
      (node (ref "U1") (pin "41") (pinfunction "GND_41") (pintype "passive"))
      (node (ref "U2") (pin "4") (pinfunction "GND_4") (pintype "passive"))
      (node (ref "U3") (pin "2") (pinfunction "2_2") (pintype "passive"))
    )
    (net (code "44") (name "Net-(D1-Pad2)") (class "Default")
      (node (ref "D1") (pin "2") (pinfunction "2_2") (pintype "passive"))
      (node (ref "R54") (pin "2") (pinfunction "2_2") (pintype "passive"))
    )
    (net (code "45") (name "Net-(J1-CC1)") (class "Default")
      (node (ref "J1") (pin "A5") (pinfunction "CC1_A5") (pintype "passive"))
      (node (ref "R1") (pin "2") (pinfunction "2_2") (pintype "passive"))
    )
    (net (code "46") (name "Net-(J1-CC2)") (class "Default")
      (node (ref "J1") (pin "B5") (pinfunction "CC2_B5") (pintype "passive"))
      (node (ref "R2") (pin "2") (pinfunction "2_2") (pintype "passive"))
    )
    (net (code "47") (name "Net-(R10-Pad1)") (class "Default")
      (node (ref "R10") (pin "1") (pinfunction "1_1") (pintype "passive"))
      (node (ref "R4") (pin "2") (pinfunction "2_2") (pintype "passive"))
      (node (ref "R9") (pin "2") (pinfunction "2_2") (pintype "passive"))
    )
    (net (code "48") (name "Net-(R10-Pad2)") (class "Default")
      (node (ref "R10") (pin "2") (pinfunction "2_2") (pintype "passive"))
      (node (ref "R11") (pin "1") (pinfunction "1_1") (pintype "passive"))
      (node (ref "R5") (pin "2") (pinfunction "2_2") (pintype "passive"))
    )
    (net (code "49") (name "Net-(R11-Pad2)") (class "Default")
      (node (ref "R11") (pin "2") (pinfunction "2_2") (pintype "passive"))
      (node (ref "R12") (pin "1") (pinfunction "1_1") (pintype "passive"))
      (node (ref "R6") (pin "2") (pinfunction "2_2") (pintype "passive"))
    )
    (net (code "50") (name "Net-(R13-Pad2)") (class "Default")
      (node (ref "R13") (pin "2") (pinfunction "2_2") (pintype "passive"))
      (node (ref "R3") (pin "2") (pinfunction "2_2") (pintype "passive"))
      (node (ref "R9") (pin "1") (pinfunction "1_1") (pintype "passive"))
    )
    (net (code "51") (name "Net-(R16-Pad2)") (class "Default")
      (node (ref "R16") (pin "2") (pinfunction "2_2") (pintype "passive"))
      (node (ref "R22") (pin "1") (pinfunction "1_1") (pintype "passive"))
      (node (ref "R26") (pin "2") (pinfunction "2_2") (pintype "passive"))
    )
    (net (code "52") (name "Net-(R17-Pad2)") (class "Default")
      (node (ref "R17") (pin "2") (pinfunction "2_2") (pintype "passive"))
      (node (ref "R22") (pin "2") (pinfunction "2_2") (pintype "passive"))
      (node (ref "R23") (pin "1") (pinfunction "1_1") (pintype "passive"))
    )
    (net (code "53") (name "Net-(R18-Pad2)") (class "Default")
      (node (ref "R18") (pin "2") (pinfunction "2_2") (pintype "passive"))
      (node (ref "R23") (pin "2") (pinfunction "2_2") (pintype "passive"))
      (node (ref "R24") (pin "1") (pinfunction "1_1") (pintype "passive"))
    )
    (net (code "54") (name "Net-(R19-Pad2)") (class "Default")
      (node (ref "R19") (pin "2") (pinfunction "2_2") (pintype "passive"))
      (node (ref "R24") (pin "2") (pinfunction "2_2") (pintype "passive"))
      (node (ref "R25") (pin "1") (pinfunction "1_1") (pintype "passive"))
    )
    (net (code "55") (name "Net-(R20-Pad2)") (class "Default")
      (node (ref "R20") (pin "2") (pinfunction "2_2") (pintype "passive"))
      (node (ref "R25") (pin "2") (pinfunction "2_2") (pintype "passive"))
      (node (ref "R46") (pin "1") (pinfunction "1_1") (pintype "passive"))
    )
    (net (code "56") (name "Net-(R28-Pad2)") (class "Default")
      (node (ref "R28") (pin "2") (pinfunction "2_2") (pintype "passive"))
      (node (ref "R33") (pin "1") (pinfunction "1_1") (pintype "passive"))
      (node (ref "R37") (pin "2") (pinfunction "2_2") (pintype "passive"))
    )
    (net (code "57") (name "Net-(R29-Pad2)") (class "Default")
      (node (ref "R29") (pin "2") (pinfunction "2_2") (pintype "passive"))
      (node (ref "R33") (pin "2") (pinfunction "2_2") (pintype "passive"))
      (node (ref "R34") (pin "1") (pinfunction "1_1") (pintype "passive"))
    )
    (net (code "58") (name "Net-(R30-Pad2)") (class "Default")
      (node (ref "R30") (pin "2") (pinfunction "2_2") (pintype "passive"))
      (node (ref "R34") (pin "2") (pinfunction "2_2") (pintype "passive"))
      (node (ref "R35") (pin "1") (pinfunction "1_1") (pintype "passive"))
    )
    (net (code "59") (name "Net-(R31-Pad2)") (class "Default")
      (node (ref "R31") (pin "2") (pinfunction "2_2") (pintype "passive"))
      (node (ref "R35") (pin "2") (pinfunction "2_2") (pintype "passive"))
      (node (ref "R36") (pin "1") (pinfunction "1_1") (pintype "passive"))
    )
    (net (code "60") (name "Net-(U2-BST)") (class "Default")
      (node (ref "C1") (pin "2") (pinfunction "2_2") (pintype "passive"))
      (node (ref "U2") (pin "6") (pinfunction "BST_6") (pintype "passive"))
    )
    (net (code "61") (name "Net-(U2-SW)") (class "Default")
      (node (ref "C1") (pin "1") (pinfunction "1_1") (pintype "passive"))
      (node (ref "L1") (pin "1") (pinfunction "1_1") (pintype "passive"))
      (node (ref "U2") (pin "5") (pinfunction "SW_5") (pintype "passive"))
    )
    (net (code "62") (name "VBUS") (class "Default")
      (node (ref "C2") (pin "2") (pinfunction "2_2") (pintype "passive"))
      (node (ref "C8") (pin "2") (pinfunction "2_2") (pintype "passive"))
      (node (ref "FB1") (pin "1") (pinfunction "1_1") (pintype "passive"))
      (node (ref "J1") (pin "A4_B9") (pinfunction "VBUS_A4_B9") (pintype "passive"))
      (node (ref "J1") (pin "B4_A9") (pinfunction "VBUS_B4_A9") (pintype "passive"))
      (node (ref "U3") (pin "5") (pinfunction "5_5") (pintype "passive"))
    )
    (net (code "63") (name "unconnected-(J1-SBU1-PadA8)") (class "Default")
      (node (ref "J1") (pin "A8") (pinfunction "SBU1_A8") (pintype "passive+no_connect"))
    )
    (net (code "64") (name "unconnected-(J1-SBU2-PadB8)") (class "Default")
      (node (ref "J1") (pin "B8") (pinfunction "SBU2_B8") (pintype "passive+no_connect"))
    )
    (net (code "65") (name "unconnected-(J2-Pad4)") (class "Default")
      (node (ref "J2") (pin "4") (pinfunction "4_4") (pintype "passive+no_connect"))
    )
    (net (code "66") (name "unconnected-(J2-Pad11)") (class "Default")
      (node (ref "J2") (pin "11") (pinfunction "11_11") (pintype "passive+no_connect"))
    )
    (net (code "67") (name "unconnected-(J2-Pad12)") (class "Default")
      (node (ref "J2") (pin "12") (pinfunction "12_12") (pintype "passive+no_connect"))
    )
    (net (code "68") (name "unconnected-(J2-Pad15)") (class "Default")
      (node (ref "J2") (pin "15") (pinfunction "15_15") (pintype "passive+no_connect"))
    )
    (net (code "69") (name "unconnected-(U1-IO39-Pad32)") (class "Default")
      (node (ref "U1") (pin "32") (pinfunction "IO39_32") (pintype "passive+no_connect"))
    )
    (net (code "70") (name "unconnected-(U1-IO40-Pad33)") (class "Default")
      (node (ref "U1") (pin "33") (pinfunction "IO40_33") (pintype "passive+no_connect"))
    )
    (net (code "71") (name "unconnected-(U1-IO41-Pad34)") (class "Default")
      (node (ref "U1") (pin "34") (pinfunction "IO41_34") (pintype "passive+no_connect"))
    )
    (net (code "72") (name "unconnected-(U1-IO42-Pad35)") (class "Default")
      (node (ref "U1") (pin "35") (pinfunction "IO42_35") (pintype "passive+no_connect"))
    )
    (net (code "73") (name "unconnected-(U1-IO45-Pad26)") (class "Default")
      (node (ref "U1") (pin "26") (pinfunction "IO45_26") (pintype "passive+no_connect"))
    )
  )
)
